# Ali_CC_Regolabile_OpAmp_PNP.net
KiCad netlist of a schematic drawn in EAGLE
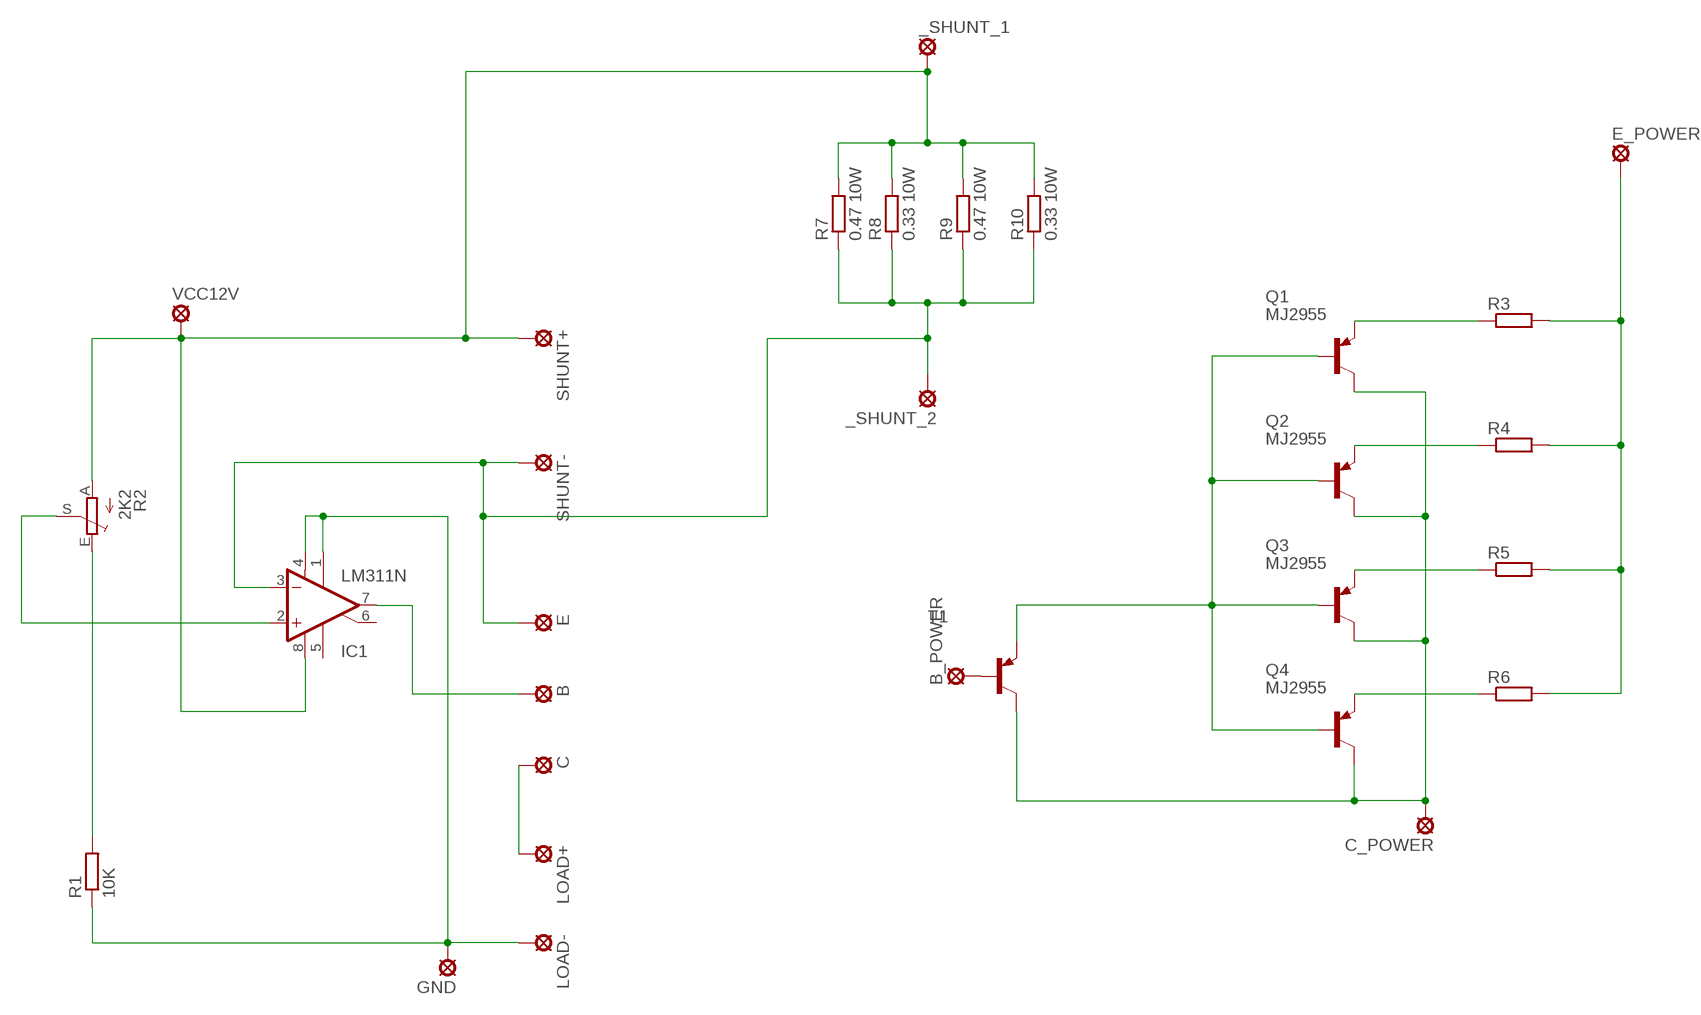
[diagram p0: schematic, sheet 1]

(export (version "E")
  (design (tool "Eeschema 10.0.6"))
  (components
    (comp (ref "B")
      (value "SE14")
      (footprint "eagle-import:SE14")
      (libsource (lib "eagle-import") (part "SE14"))
    )
    (comp (ref "B_POWER")
      (value "LSP10")
      (footprint "eagle-import:LSP10")
      (libsource (lib "eagle-import") (part "LSP10"))
    )
    (comp (ref "C")
      (value "SE14")
      (footprint "eagle-import:SE14")
      (libsource (lib "eagle-import") (part "SE14"))
    )
    (comp (ref "C_POWER")
      (value "LSP10")
      (footprint "eagle-import:LSP10")
      (libsource (lib "eagle-import") (part "LSP10"))
    )
    (comp (ref "E")
      (value "SE14")
      (footprint "eagle-import:SE14")
      (libsource (lib "eagle-import") (part "SE14"))
    )
    (comp (ref "E_POWER")
      (value "LSP10")
      (footprint "eagle-import:LSP10")
      (libsource (lib "eagle-import") (part "LSP10"))
    )
    (comp (ref "GND")
      (value "SE14")
      (footprint "eagle-import:SE14")
      (libsource (lib "eagle-import") (part "SE14"))
    )
    (comp (ref "IC1")
      (value "LM311N")
      (footprint "eagle-import:DIL08")
      (libsource (lib "eagle-import") (part "LM311N"))
    )
    (comp (ref "LOAD+")
      (value "SE14")
      (footprint "eagle-import:SE14")
      (libsource (lib "eagle-import") (part "SE14"))
    )
    (comp (ref "LOAD-")
      (value "SE14")
      (footprint "eagle-import:SE14")
      (libsource (lib "eagle-import") (part "SE14"))
    )
    (comp (ref "Q1")
      (value "MJ2955")
      (footprint "eagle-import:TO3")
      (libsource (lib "eagle-import") (part "MJ2955"))
    )
    (comp (ref "Q2")
      (value "MJ2955")
      (footprint "eagle-import:TO3")
      (libsource (lib "eagle-import") (part "MJ2955"))
    )
    (comp (ref "Q3")
      (value "MJ2955")
      (footprint "eagle-import:TO3")
      (libsource (lib "eagle-import") (part "MJ2955"))
    )
    (comp (ref "Q4")
      (value "MJ2955")
      (footprint "eagle-import:TO3")
      (libsource (lib "eagle-import") (part "MJ2955"))
    )
    (comp (ref "R1")
      (value "10K")
      (footprint "eagle-import:0207_15")
      (libsource (lib "eagle-import") (part "R-EU_0207/15"))
    )
    (comp (ref "R2")
      (value "2K2")
      (footprint "eagle-import:CIP20C-6MM")
      (libsource (lib "eagle-import") (part "TRIM_EU-CIP20C-6MM"))
    )
    (comp (ref "R3")
      (value "R-EU_VTA53")
      (footprint "eagle-import:VTA53")
      (libsource (lib "eagle-import") (part "R-EU_VTA53"))
    )
    (comp (ref "R4")
      (value "R-EU_VTA53")
      (footprint "eagle-import:VTA53")
      (libsource (lib "eagle-import") (part "R-EU_VTA53"))
    )
    (comp (ref "R5")
      (value "R-EU_VTA53")
      (footprint "eagle-import:VTA53")
      (libsource (lib "eagle-import") (part "R-EU_VTA53"))
    )
    (comp (ref "R6")
      (value "R-EU_VTA53")
      (footprint "eagle-import:VTA53")
      (libsource (lib "eagle-import") (part "R-EU_VTA53"))
    )
    (comp (ref "R7")
      (value "0.47 10W")
      (footprint "eagle-import:VTA53")
      (libsource (lib "eagle-import") (part "R-EU_VTA53"))
    )
    (comp (ref "R8")
      (value "0.33 10W")
      (footprint "eagle-import:VTA53")
      (libsource (lib "eagle-import") (part "R-EU_VTA53"))
    )
    (comp (ref "R9")
      (value "0.47 10W")
      (footprint "eagle-import:VTA53")
      (libsource (lib "eagle-import") (part "R-EU_VTA53"))
    )
    (comp (ref "R10")
      (value "0.33 10W")
      (footprint "eagle-import:VTA53")
      (libsource (lib "eagle-import") (part "R-EU_VTA53"))
    )
    (comp (ref "SHUNT+")
      (value "SE14")
      (footprint "eagle-import:SE14")
      (libsource (lib "eagle-import") (part "SE14"))
    )
    (comp (ref "SHUNT-")
      (value "SE14")
      (footprint "eagle-import:SE14")
      (libsource (lib "eagle-import") (part "SE14"))
    )
    (comp (ref "T1")
      (value "BC558A-PNP-TO92-EBC")
      (footprint "eagle-import:TO92-EBC")
      (libsource (lib "eagle-import") (part "-PNP-TO92-EBCBC558A"))
    )
    (comp (ref "VCC12V")
      (value "SE14")
      (footprint "eagle-import:SE14")
      (libsource (lib "eagle-import") (part "SE14"))
    )
    (comp (ref "_SHUNT_1")
      (value "LSP10")
      (footprint "eagle-import:LSP10")
      (libsource (lib "eagle-import") (part "LSP10"))
    )
    (comp (ref "_SHUNT_2")
      (value "LSP10")
      (footprint "eagle-import:LSP10")
      (libsource (lib "eagle-import") (part "LSP10"))
    )
  )
  (nets
    (net (code "1") (name "Net-(B_POWER-PadMP)") (class "Default")
      (node (ref "B_POWER") (pin "MP") (pinfunction "MP_MP") (pintype "passive"))
      (node (ref "T1") (pin "B") (pinfunction "B_B") (pintype "passive"))
    )
    (net (code "2") (name "Net-(C-PadMP)") (class "Default")
      (node (ref "C") (pin "MP") (pinfunction "MP_MP") (pintype "passive"))
      (node (ref "LOAD+") (pin "MP") (pinfunction "MP_MP") (pintype "passive"))
    )
    (net (code "3") (name "Net-(C_POWER-PadMP)") (class "Default")
      (node (ref "C_POWER") (pin "MP") (pinfunction "MP_MP") (pintype "passive"))
      (node (ref "Q1") (pin "C") (pinfunction "C_C") (pintype "passive"))
      (node (ref "Q1") (pin "C/") (pinfunction "C_C/") (pintype "passive"))
      (node (ref "Q2") (pin "C") (pinfunction "C_C") (pintype "passive"))
      (node (ref "Q2") (pin "C/") (pinfunction "C_C/") (pintype "passive"))
      (node (ref "Q3") (pin "C") (pinfunction "C_C") (pintype "passive"))
      (node (ref "Q3") (pin "C/") (pinfunction "C_C/") (pintype "passive"))
      (node (ref "Q4") (pin "C") (pinfunction "C_C") (pintype "passive"))
      (node (ref "Q4") (pin "C/") (pinfunction "C_C/") (pintype "passive"))
      (node (ref "T1") (pin "C") (pinfunction "C_C") (pintype "passive"))
    )
    (net (code "4") (name "Net-(E_POWER-PadMP)") (class "Default")
      (node (ref "E_POWER") (pin "MP") (pinfunction "MP_MP") (pintype "passive"))
      (node (ref "R3") (pin "2") (pinfunction "2_2") (pintype "passive"))
      (node (ref "R4") (pin "2") (pinfunction "2_2") (pintype "passive"))
      (node (ref "R5") (pin "2") (pinfunction "2_2") (pintype "passive"))
      (node (ref "R6") (pin "2") (pinfunction "2_2") (pintype "passive"))
    )
    (net (code "5") (name "Net-(IC1-+IN)") (class "Default")
      (node (ref "IC1") (pin "2") (pinfunction "+IN_2") (pintype "input"))
      (node (ref "R2") (pin "S") (pinfunction "S_S") (pintype "passive"))
    )
    (net (code "6") (name "Net-(IC1--IN)") (class "Default")
      (node (ref "E") (pin "MP") (pinfunction "MP_MP") (pintype "passive"))
      (node (ref "IC1") (pin "3") (pinfunction "-IN_3") (pintype "input"))
      (node (ref "R10") (pin "1") (pinfunction "1_1") (pintype "passive"))
      (node (ref "R7") (pin "1") (pinfunction "1_1") (pintype "passive"))
      (node (ref "R8") (pin "1") (pinfunction "1_1") (pintype "passive"))
      (node (ref "R9") (pin "1") (pinfunction "1_1") (pintype "passive"))
      (node (ref "SHUNT-") (pin "MP") (pinfunction "MP_MP") (pintype "passive"))
      (node (ref "_SHUNT_2") (pin "MP") (pinfunction "MP_MP") (pintype "passive"))
    )
    (net (code "7") (name "Net-(IC1-GND)") (class "Default")
      (node (ref "GND") (pin "MP") (pinfunction "MP_MP") (pintype "passive"))
      (node (ref "IC1") (pin "1") (pinfunction "GND_1") (pintype "passive"))
      (node (ref "IC1") (pin "4") (pinfunction "V-_4") (pintype "power_in"))
      (node (ref "LOAD-") (pin "MP") (pinfunction "MP_MP") (pintype "passive"))
      (node (ref "R1") (pin "1") (pinfunction "1_1") (pintype "passive"))
    )
    (net (code "8") (name "Net-(IC1-OUT)") (class "Default")
      (node (ref "B") (pin "MP") (pinfunction "MP_MP") (pintype "passive"))
      (node (ref "IC1") (pin "7") (pinfunction "OUT_7") (pintype "output"))
    )
    (net (code "9") (name "Net-(IC1-V+)") (class "Default")
      (node (ref "IC1") (pin "8") (pinfunction "V+_8") (pintype "power_in"))
      (node (ref "R10") (pin "2") (pinfunction "2_2") (pintype "passive"))
      (node (ref "R2") (pin "A") (pinfunction "A_A") (pintype "passive"))
      (node (ref "R7") (pin "2") (pinfunction "2_2") (pintype "passive"))
      (node (ref "R8") (pin "2") (pinfunction "2_2") (pintype "passive"))
      (node (ref "R9") (pin "2") (pinfunction "2_2") (pintype "passive"))
      (node (ref "SHUNT+") (pin "MP") (pinfunction "MP_MP") (pintype "passive"))
      (node (ref "VCC12V") (pin "MP") (pinfunction "MP_MP") (pintype "passive"))
      (node (ref "_SHUNT_1") (pin "MP") (pinfunction "MP_MP") (pintype "passive"))
    )
    (net (code "10") (name "Net-(Q1-PadB)") (class "Default")
      (node (ref "Q1") (pin "B") (pinfunction "B_B") (pintype "passive"))
      (node (ref "Q2") (pin "B") (pinfunction "B_B") (pintype "passive"))
      (node (ref "Q3") (pin "B") (pinfunction "B_B") (pintype "passive"))
      (node (ref "Q4") (pin "B") (pinfunction "B_B") (pintype "passive"))
      (node (ref "T1") (pin "E") (pinfunction "E_E") (pintype "passive"))
    )
    (net (code "11") (name "Net-(Q1-PadE)") (class "Default")
      (node (ref "Q1") (pin "E") (pinfunction "E_E") (pintype "passive"))
      (node (ref "R3") (pin "1") (pinfunction "1_1") (pintype "passive"))
    )
    (net (code "12") (name "Net-(Q2-PadE)") (class "Default")
      (node (ref "Q2") (pin "E") (pinfunction "E_E") (pintype "passive"))
      (node (ref "R4") (pin "1") (pinfunction "1_1") (pintype "passive"))
    )
    (net (code "13") (name "Net-(Q3-PadE)") (class "Default")
      (node (ref "Q3") (pin "E") (pinfunction "E_E") (pintype "passive"))
      (node (ref "R5") (pin "1") (pinfunction "1_1") (pintype "passive"))
    )
    (net (code "14") (name "Net-(Q4-PadE)") (class "Default")
      (node (ref "Q4") (pin "E") (pinfunction "E_E") (pintype "passive"))
      (node (ref "R6") (pin "1") (pinfunction "1_1") (pintype "passive"))
    )
    (net (code "15") (name "Net-(R1-Pad2)") (class "Default")
      (node (ref "R1") (pin "2") (pinfunction "2_2") (pintype "passive"))
      (node (ref "R2") (pin "E") (pinfunction "E_E") (pintype "passive"))
    )
    (net (code "16") (name "unconnected-(IC1-ON-Pad5)") (class "Default")
      (node (ref "IC1") (pin "5") (pinfunction "ON_5") (pintype "passive"))
    )
    (net (code "17") (name "unconnected-(IC1-ON{slash}STR-Pad6)") (class "Default")
      (node (ref "IC1") (pin "6") (pinfunction "ON/STR_6") (pintype "passive"))
    )
  )
)
